# EASYEDA_Project_IOX_77_devboard_CG.net
KiCad netlist of a schematic drawn in EasyEDA Pro
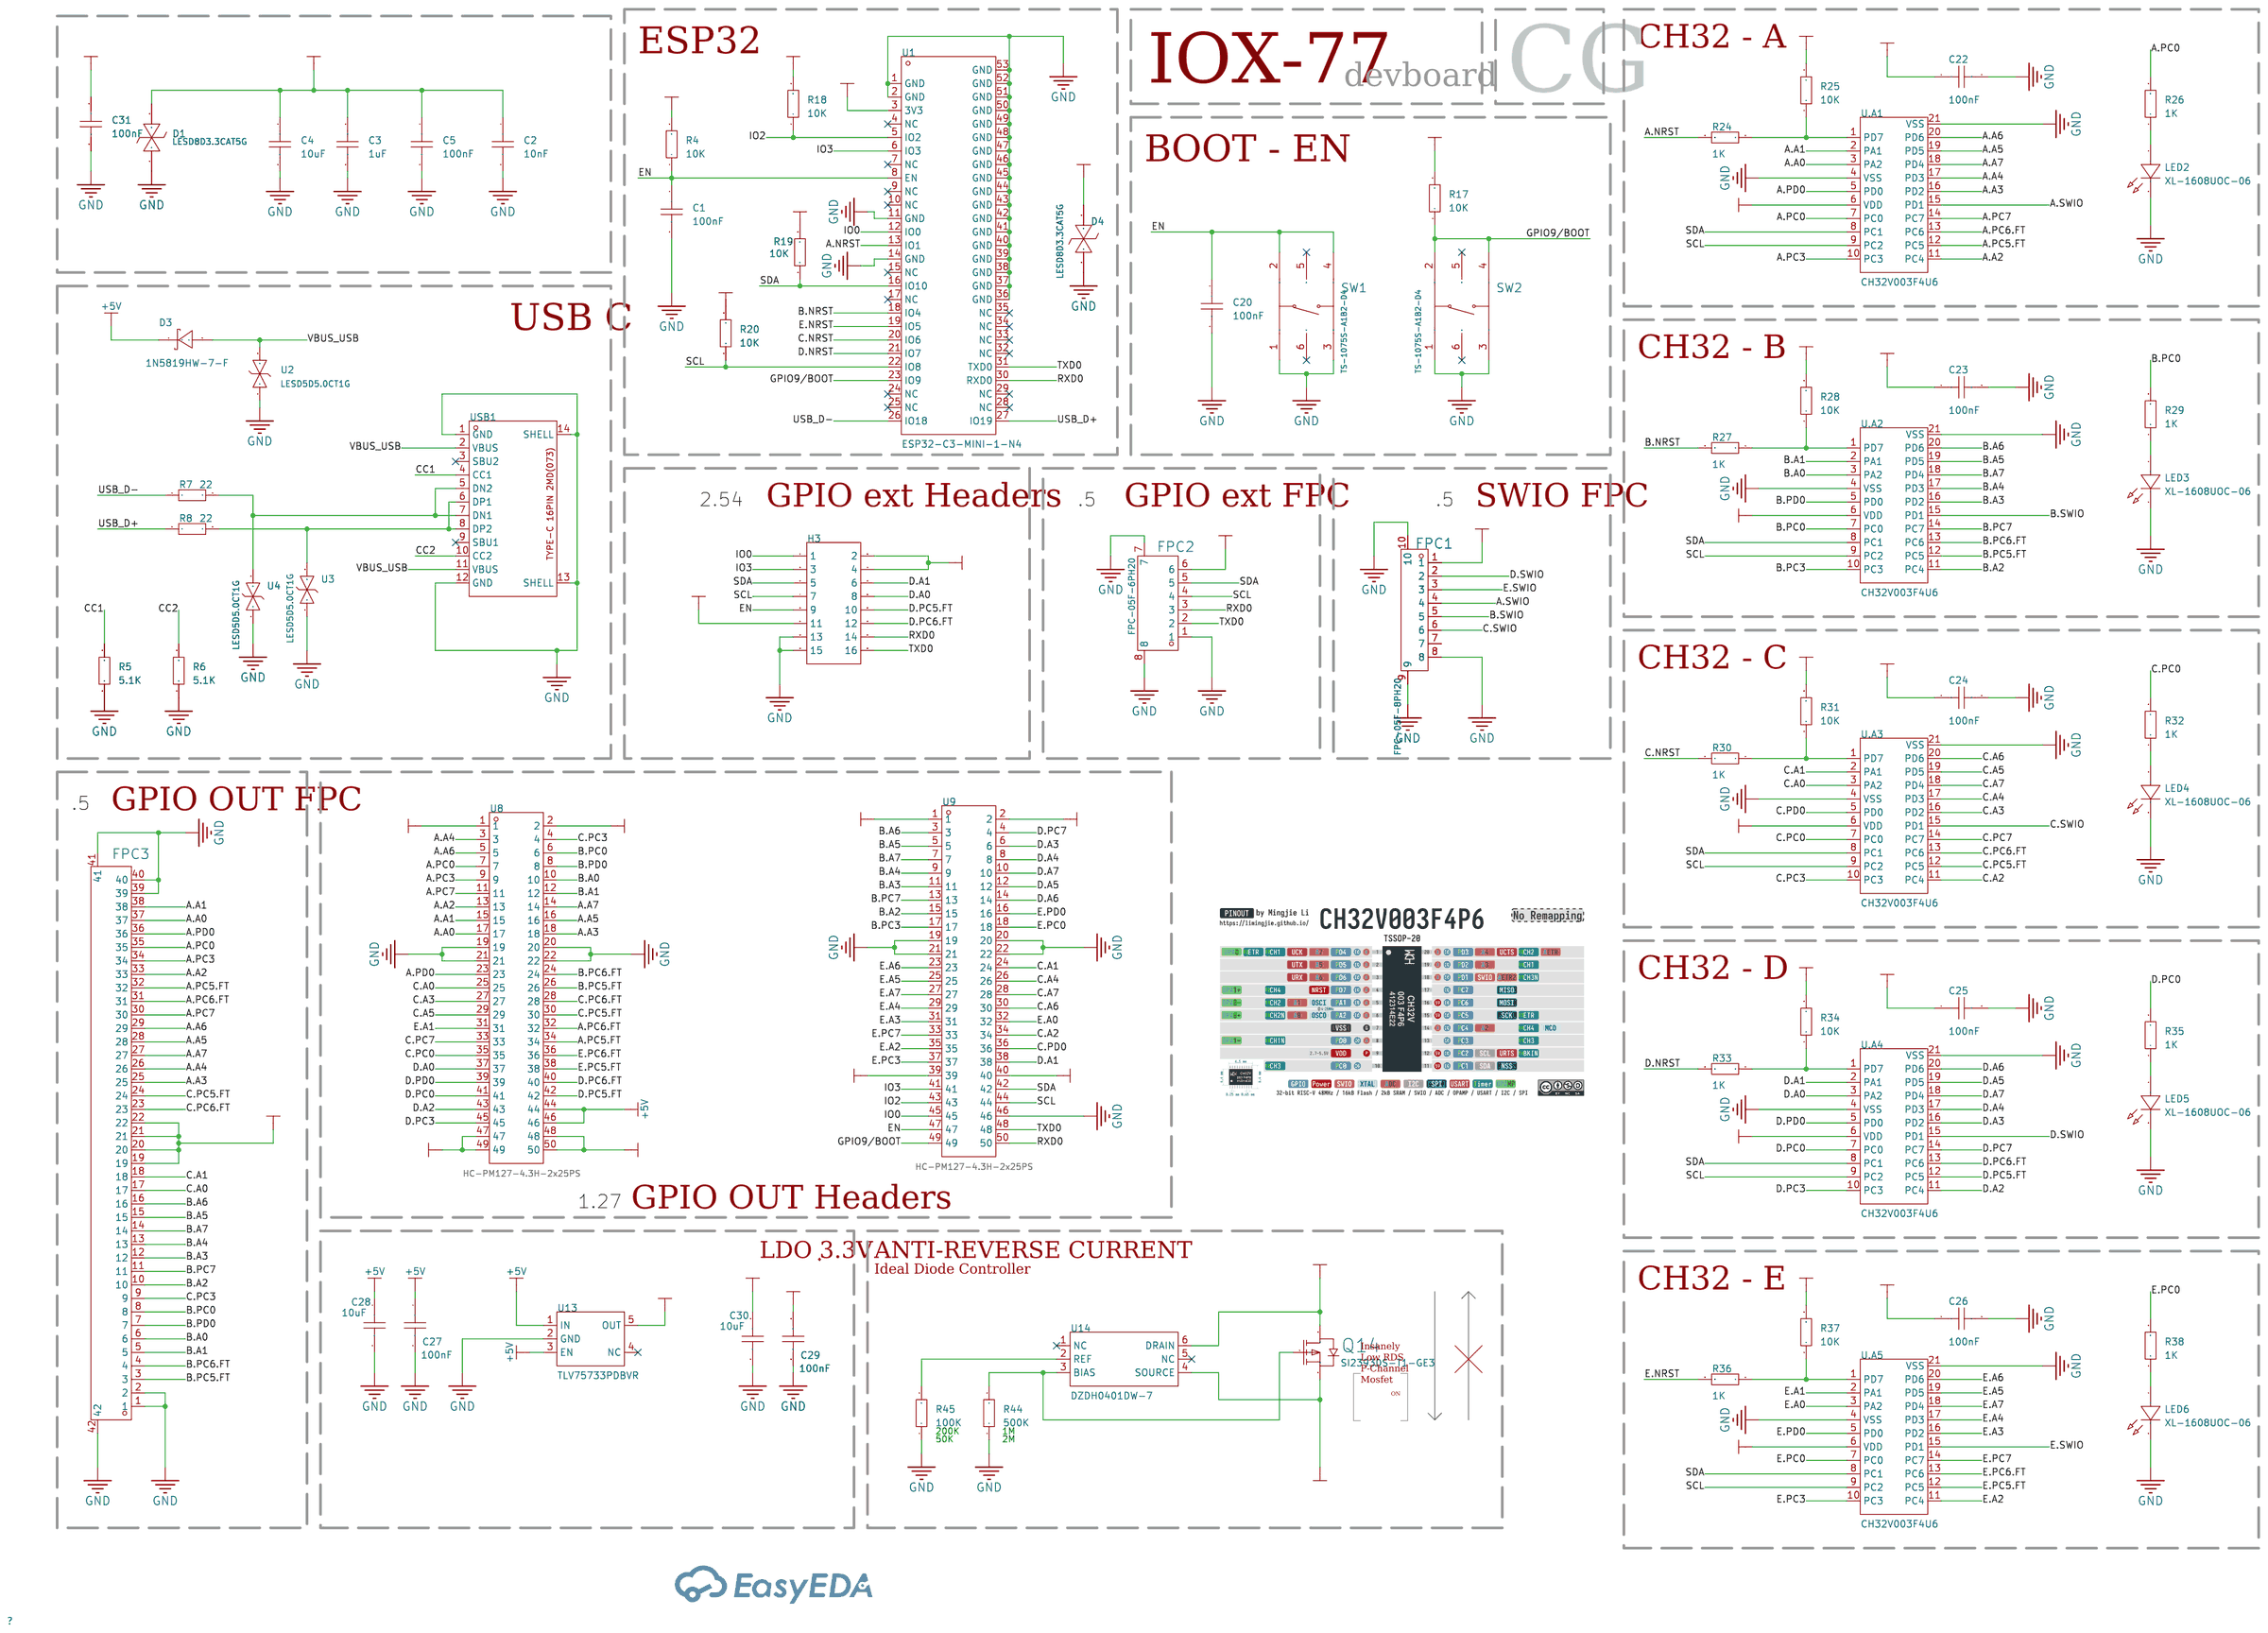
[diagram p0: schematic sheet]

(export (version "E")
  (design (tool "Eeschema 10.0.6"))
  (components
    (comp (ref "C1")
      (value "100nF")
      (footprint "easyedapro:C0603")
      (libsource (lib "easyedapro") (part "CAP"))
    )
    (comp (ref "C2")
      (value "10nF")
      (footprint "easyedapro:C0603")
      (description "Capacitance:10nF Tolerance:±10% Tolerance:±10% Voltage Rating:16V Temperature Coefficient:X7R")
      (fields
        (field (name "Manufacturer Part") "CC0603KRX7R7BB103")
        (field (name "Manufacturer") "YAGEO(国巨)")
      )
      (libsource (lib "easyedapro") (part "CAP"))
    )
    (comp (ref "C3")
      (value "1uF")
      (footprint "easyedapro:C0603")
      (description "Capacitance:1uF Tolerance:±10% Tolerance:±10% Voltage Rating:16V Temperature Coefficient:X5R")
      (fields
        (field (name "Manufacturer Part") "CL10A105KO8NNNC")
        (field (name "Manufacturer") "SAMSUNG(三星)")
      )
      (libsource (lib "easyedapro") (part "CAP"))
    )
    (comp (ref "C4")
      (value "10uF")
      (footprint "easyedapro:C0603")
      (description "Capacitance:10uF Tolerance:±10% Tolerance:±10% Voltage Rating:16V Temperature Coefficient:X5R")
      (fields
        (field (name "Manufacturer Part") "CL21A106KOQNNNE")
        (field (name "Manufacturer") "SAMSUNG(三星)")
      )
      (libsource (lib "easyedapro") (part "CAP"))
    )
    (comp (ref "C5")
      (value "100nF")
      (footprint "easyedapro:C0603")
      (description "Capacitance:100nF Tolerance:±10% Tolerance:±10% Voltage Rating:16V Temperature Coefficient:X7R")
      (fields
        (field (name "Manufacturer Part") "CL10B104KO8NNNC")
        (field (name "Manufacturer") "SAMSUNG(三星)")
      )
      (libsource (lib "easyedapro") (part "CAP"))
    )
    (comp (ref "C20")
      (value "100nF")
      (footprint "easyedapro:C0603")
      (description "Capacitance:100nF Tolerance:±10% Tolerance:±10% Voltage Rating:16V Temperature Coefficient:X7R")
      (fields
        (field (name "Manufacturer Part") "CL10B104KO8NNNC")
        (field (name "Manufacturer") "SAMSUNG(三星)")
      )
      (libsource (lib "easyedapro") (part "CAP"))
    )
    (comp (ref "C22")
      (value "100nF")
      (footprint "easyedapro:C0603")
      (description "Capacitance:100nF Tolerance:±10% Tolerance:±10% Voltage Rating:16V Temperature Coefficient:X7R")
      (fields
        (field (name "Manufacturer Part") "CL10B104KO8NNNC")
        (field (name "Manufacturer") "SAMSUNG(三星)")
      )
      (libsource (lib "easyedapro") (part "CAP"))
    )
    (comp (ref "C23")
      (value "100nF")
      (footprint "easyedapro:C0603")
      (description "Capacitance:100nF Tolerance:±10% Tolerance:±10% Voltage Rating:16V Temperature Coefficient:X7R")
      (fields
        (field (name "Manufacturer Part") "CL10B104KO8NNNC")
        (field (name "Manufacturer") "SAMSUNG(三星)")
      )
      (libsource (lib "easyedapro") (part "CAP"))
    )
    (comp (ref "C24")
      (value "100nF")
      (footprint "easyedapro:C0603")
      (description "Capacitance:100nF Tolerance:±10% Tolerance:±10% Voltage Rating:16V Temperature Coefficient:X7R")
      (fields
        (field (name "Manufacturer Part") "CL10B104KO8NNNC")
        (field (name "Manufacturer") "SAMSUNG(三星)")
      )
      (libsource (lib "easyedapro") (part "CAP"))
    )
    (comp (ref "C25")
      (value "100nF")
      (footprint "easyedapro:C0603")
      (description "Capacitance:100nF Tolerance:±10% Tolerance:±10% Voltage Rating:16V Temperature Coefficient:X7R")
      (fields
        (field (name "Manufacturer Part") "CL10B104KO8NNNC")
        (field (name "Manufacturer") "SAMSUNG(三星)")
      )
      (libsource (lib "easyedapro") (part "CAP"))
    )
    (comp (ref "C26")
      (value "100nF")
      (footprint "easyedapro:C0603")
      (description "Capacitance:100nF Tolerance:±10% Tolerance:±10% Voltage Rating:16V Temperature Coefficient:X7R")
      (fields
        (field (name "Manufacturer Part") "CL10B104KO8NNNC")
        (field (name "Manufacturer") "SAMSUNG(三星)")
      )
      (libsource (lib "easyedapro") (part "CAP"))
    )
    (comp (ref "C27")
      (value "100nF")
      (footprint "easyedapro:C0603")
      (description "Capacitance:100nF Tolerance:±10% Tolerance:±10% Voltage Rating:16V Temperature Coefficient:X7R")
      (fields
        (field (name "Manufacturer Part") "CL10B104KO8NNNC")
        (field (name "Manufacturer") "SAMSUNG(三星)")
      )
      (libsource (lib "easyedapro") (part "CAP"))
    )
    (comp (ref "C28")
      (value "10uF")
      (footprint "easyedapro:C0603")
      (description "Capacitance:10uF Tolerance:±10% Tolerance:±10% Voltage Rating:16V Temperature Coefficient:X5R")
      (fields
        (field (name "Manufacturer Part") "CL21A106KOQNNNE")
        (field (name "Manufacturer") "SAMSUNG(三星)")
      )
      (libsource (lib "easyedapro") (part "CAP"))
    )
    (comp (ref "C29")
      (value "100nF")
      (footprint "easyedapro:C0603")
      (description "Capacitance:100nF Tolerance:±10% Tolerance:±10% Voltage Rating:16V Temperature Coefficient:X7R")
      (fields
        (field (name "Manufacturer Part") "CL10B104KO8NNNC")
        (field (name "Manufacturer") "SAMSUNG(三星)")
      )
      (libsource (lib "easyedapro") (part "CAP"))
    )
    (comp (ref "C30")
      (value "10uF")
      (footprint "easyedapro:C0603")
      (description "Capacitance:10uF Tolerance:±10% Tolerance:±10% Voltage Rating:16V Temperature Coefficient:X5R")
      (fields
        (field (name "Manufacturer Part") "CL21A106KOQNNNE")
        (field (name "Manufacturer") "SAMSUNG(三星)")
      )
      (libsource (lib "easyedapro") (part "CAP"))
    )
    (comp (ref "C31")
      (value "100nF")
      (footprint "easyedapro:C0603")
      (description "Capacitance:10nF Tolerance:±10% Tolerance:±10% Voltage Rating:16V Temperature Coefficient:X7R")
      (fields
        (field (name "Manufacturer Part") "CC0603KRX7R7BB103")
        (field (name "Manufacturer") "YAGEO(国巨)")
      )
      (libsource (lib "easyedapro") (part "CAP"))
    )
    (comp (ref "D1")
      (value "LESD8D3.3CAT5G")
      (footprint "easyedapro:SOD-882_L1.0-W0.6-BI")
      (fields (field (name "Manufacturer") "FUXINSEMI(富芯森美)"))
      (libsource (lib "easyedapro") (part "LESD8D3.3CAT5G_C5563754"))
    )
    (comp (ref "D3")
      (value "1N5819HW-7-F")
      (footprint "easyedapro:SOD-123_L2.7-W1.6-LS3.7-RD")
      (fields (field (name "Manufacturer") "DIODES(美台)"))
      (libsource (lib "easyedapro") (part "1N5819HW-7-F"))
    )
    (comp (ref "D4")
      (value "LESD8D3.3CAT5G")
      (footprint "easyedapro:SOD-882_L1.0-W0.6-BI")
      (fields (field (name "Manufacturer") "FUXINSEMI(富芯森美)"))
      (libsource (lib "easyedapro") (part "LESD8D3.3CAT5G_C5563754"))
    )
    (comp (ref "FPC1")
      (value "FPC-05F-8PH20")
      (footprint "easyedapro:FPC-SMD_8P-P0.50_FPC-05F-8PH20")
      (fields (field (name "Manufacturer") "XUNPU(讯普)"))
      (libsource (lib "easyedapro") (part "FPC-05F-8PH20"))
    )
    (comp (ref "FPC2")
      (value "FPC-05F-6PH20")
      (footprint "easyedapro:FPC-SMD_6P-P0.50_XUNPU_FPC-05F-6PH20")
      (fields (field (name "Manufacturer") "XUNPU(讯普)"))
      (libsource (lib "easyedapro") (part "FPC-05F-6PH20"))
    )
    (comp (ref "FPC3")
      (value "FPC-05F-40PH20")
      (footprint "easyedapro:FPC-SMD_40P-P0.50_FPC-05F-40PH20")
      (fields (field (name "Manufacturer") "XUNPU(讯普)"))
      (libsource (lib "easyedapro") (part "FPC-05F-40PH20"))
    )
    (comp (ref "H3")
      (value "~")
      (footprint "easyedapro:HDR-TH_16P-P2.54-V-M-R2-C8-S2.54")
      (libsource (lib "easyedapro") (part "HDR-M-2.54_2x8"))
    )
    (comp (ref "LED2")
      (value "XL-1608UOC-06")
      (footprint "easyedapro:LED0603-R-RD_ORANGE")
      (fields (field (name "Manufacturer") "XINGLIGHT(成兴光)"))
      (libsource (lib "easyedapro") (part "XL-1608UOC-06"))
    )
    (comp (ref "LED3")
      (value "XL-1608UOC-06")
      (footprint "easyedapro:LED0603-R-RD_ORANGE")
      (fields (field (name "Manufacturer") "XINGLIGHT(成兴光)"))
      (libsource (lib "easyedapro") (part "XL-1608UOC-06"))
    )
    (comp (ref "LED4")
      (value "XL-1608UOC-06")
      (footprint "easyedapro:LED0603-R-RD_ORANGE")
      (fields (field (name "Manufacturer") "XINGLIGHT(成兴光)"))
      (libsource (lib "easyedapro") (part "XL-1608UOC-06"))
    )
    (comp (ref "LED5")
      (value "XL-1608UOC-06")
      (footprint "easyedapro:LED0603-R-RD_ORANGE")
      (fields (field (name "Manufacturer") "XINGLIGHT(成兴光)"))
      (libsource (lib "easyedapro") (part "XL-1608UOC-06"))
    )
    (comp (ref "LED6")
      (value "XL-1608UOC-06")
      (footprint "easyedapro:LED0603-R-RD_ORANGE")
      (fields (field (name "Manufacturer") "XINGLIGHT(成兴光)"))
      (libsource (lib "easyedapro") (part "XL-1608UOC-06"))
    )
    (comp (ref "Q14")
      (value "SI2393DS-T1-GE3")
      (footprint "easyedapro:SOT-23-3_L2.9-W1.3-P1.90-LS2.4-BR")
      (fields (field (name "Manufacturer") "VISHAY(威世)"))
      (libsource (lib "easyedapro") (part "SI2393DS-T1-GE3"))
    )
    (comp (ref "R4") (value "10K") (footprint "easyedapro:R0603") (libsource (lib "easyedapro") (part "Res")))
    (comp (ref "R5")
      (value "5.1K")
      (footprint "easyedapro:R0603")
      (libsource (lib "easyedapro") (part "Res"))
    )
    (comp (ref "R6")
      (value "5.1K")
      (footprint "easyedapro:R0603")
      (libsource (lib "easyedapro") (part "Res"))
    )
    (comp (ref "R7") (value "22") (footprint "easyedapro:R0603") (libsource (lib "easyedapro") (part "Res")))
    (comp (ref "R8") (value "22") (footprint "easyedapro:R0603") (libsource (lib "easyedapro") (part "Res")))
    (comp (ref "R17")
      (value "10K")
      (footprint "easyedapro:R0603")
      (libsource (lib "easyedapro") (part "Res"))
    )
    (comp (ref "R18")
      (value "10K")
      (footprint "easyedapro:R0603")
      (libsource (lib "easyedapro") (part "Res"))
    )
    (comp (ref "R19")
      (value "10K")
      (footprint "easyedapro:R0603")
      (libsource (lib "easyedapro") (part "Res"))
    )
    (comp (ref "R20")
      (value "10K")
      (footprint "easyedapro:R0603")
      (libsource (lib "easyedapro") (part "Res"))
    )
    (comp (ref "R24") (value "1K") (footprint "easyedapro:R0603") (libsource (lib "easyedapro") (part "Res")))
    (comp (ref "R25")
      (value "10K")
      (footprint "easyedapro:R0603")
      (libsource (lib "easyedapro") (part "Res"))
    )
    (comp (ref "R26") (value "1K") (footprint "easyedapro:R0603") (libsource (lib "easyedapro") (part "Res")))
    (comp (ref "R27") (value "1K") (footprint "easyedapro:R0603") (libsource (lib "easyedapro") (part "Res")))
    (comp (ref "R28")
      (value "10K")
      (footprint "easyedapro:R0603")
      (libsource (lib "easyedapro") (part "Res"))
    )
    (comp (ref "R29") (value "1K") (footprint "easyedapro:R0603") (libsource (lib "easyedapro") (part "Res")))
    (comp (ref "R30") (value "1K") (footprint "easyedapro:R0603") (libsource (lib "easyedapro") (part "Res")))
    (comp (ref "R31")
      (value "10K")
      (footprint "easyedapro:R0603")
      (libsource (lib "easyedapro") (part "Res"))
    )
    (comp (ref "R32") (value "1K") (footprint "easyedapro:R0603") (libsource (lib "easyedapro") (part "Res")))
    (comp (ref "R33") (value "1K") (footprint "easyedapro:R0603") (libsource (lib "easyedapro") (part "Res")))
    (comp (ref "R34")
      (value "10K")
      (footprint "easyedapro:R0603")
      (libsource (lib "easyedapro") (part "Res"))
    )
    (comp (ref "R35") (value "1K") (footprint "easyedapro:R0603") (libsource (lib "easyedapro") (part "Res")))
    (comp (ref "R36") (value "1K") (footprint "easyedapro:R0603") (libsource (lib "easyedapro") (part "Res")))
    (comp (ref "R37")
      (value "10K")
      (footprint "easyedapro:R0603")
      (libsource (lib "easyedapro") (part "Res"))
    )
    (comp (ref "R38") (value "1K") (footprint "easyedapro:R0603") (libsource (lib "easyedapro") (part "Res")))
    (comp (ref "R44")
      (value "500K")
      (footprint "easyedapro:R0603")
      (libsource (lib "easyedapro") (part "Res"))
    )
    (comp (ref "R45")
      (value "100K")
      (footprint "easyedapro:R0603")
      (libsource (lib "easyedapro") (part "Res"))
    )
    (comp (ref "SW1")
      (value "TS-1075S-A1B2-D4")
      (footprint "easyedapro:SW-SMD_4P-L3.1-W3.1-P2.20-LS4.0")
      (fields (field (name "Manufacturer") "Yuandi(元迪)"))
      (libsource (lib "easyedapro") (part "TS-1075S-A1B2-D4"))
    )
    (comp (ref "SW2")
      (value "TS-1075S-A1B2-D4")
      (footprint "easyedapro:SW-SMD_4P-L3.1-W3.1-P2.20-LS4.0")
      (fields (field (name "Manufacturer") "Yuandi(元迪)"))
      (libsource (lib "easyedapro") (part "TS-1075S-A1B2-D4"))
    )
    (comp (ref "U.A1")
      (value "CH32V003F4U6")
      (footprint "easyedapro:QFN-20_L3.0-W3.0-P0.40-TL-EP1.7")
      (description "CPU Core:RISC-V CPU Maximum Speed:48MHz Program Storage Size:16KB Number of I/O:18 Applications:-")
      (fields (field (name "Manufacturer") "WCH(南京沁恒)"))
      (libsource (lib "easyedapro") (part "CH32V003F4U6"))
    )
    (comp (ref "U.A2")
      (value "CH32V003F4U6")
      (footprint "easyedapro:QFN-20_L3.0-W3.0-P0.40-TL-EP1.7")
      (description "CPU Core:RISC-V CPU Maximum Speed:48MHz Program Storage Size:16KB Number of I/O:18 Applications:-")
      (fields (field (name "Manufacturer") "WCH(南京沁恒)"))
      (libsource (lib "easyedapro") (part "CH32V003F4U6"))
    )
    (comp (ref "U.A3")
      (value "CH32V003F4U6")
      (footprint "easyedapro:QFN-20_L3.0-W3.0-P0.40-TL-EP1.7")
      (description "CPU Core:RISC-V CPU Maximum Speed:48MHz Program Storage Size:16KB Number of I/O:18 Applications:-")
      (fields (field (name "Manufacturer") "WCH(南京沁恒)"))
      (libsource (lib "easyedapro") (part "CH32V003F4U6"))
    )
    (comp (ref "U.A4")
      (value "CH32V003F4U6")
      (footprint "easyedapro:QFN-20_L3.0-W3.0-P0.40-TL-EP1.7")
      (description "CPU Core:RISC-V CPU Maximum Speed:48MHz Program Storage Size:16KB Number of I/O:18 Applications:-")
      (fields (field (name "Manufacturer") "WCH(南京沁恒)"))
      (libsource (lib "easyedapro") (part "CH32V003F4U6"))
    )
    (comp (ref "U.A5")
      (value "CH32V003F4U6")
      (footprint "easyedapro:QFN-20_L3.0-W3.0-P0.40-TL-EP1.7")
      (description "CPU Core:RISC-V CPU Maximum Speed:48MHz Program Storage Size:16KB Number of I/O:18 Applications:-")
      (fields (field (name "Manufacturer") "WCH(南京沁恒)"))
      (libsource (lib "easyedapro") (part "CH32V003F4U6"))
    )
    (comp (ref "U1")
      (value "ESP32-C3-MINI-1-N4")
      (footprint "easyedapro:WIFIM-SMD_ESP32-C3-MINI-1")
      (fields (field (name "Manufacturer") "ESPRESSIF(乐鑫)"))
      (libsource (lib "easyedapro") (part "ESP32-C3-MINI-1-N4"))
    )
    (comp (ref "U2")
      (value "LESD5D5.0CT1G")
      (footprint "easyedapro:SOD-523_L1.2-W0.8-LS1.6-BI")
      (fields (field (name "Manufacturer") "KUU"))
      (libsource (lib "easyedapro") (part "LESD5D5.0CT1G_C7433850"))
    )
    (comp (ref "U3")
      (value "LESD5D5.0CT1G")
      (footprint "easyedapro:SOD-523_L1.2-W0.8-LS1.6-BI")
      (fields (field (name "Manufacturer") "KUU"))
      (libsource (lib "easyedapro") (part "LESD5D5.0CT1G_C7433850"))
    )
    (comp (ref "U4")
      (value "LESD5D5.0CT1G")
      (footprint "easyedapro:SOD-523_L1.2-W0.8-LS1.6-BI")
      (fields (field (name "Manufacturer") "KUU"))
      (libsource (lib "easyedapro") (part "LESD5D5.0CT1G_C7433850"))
    )
    (comp (ref "U8")
      (value "HC-PM127-4.3H-2x25PS")
      (footprint "easyedapro:HDR-SMD_50P-P1.27-V-F-R2-C25-LS4.8")
      (fields (field (name "Manufacturer") "HC(虹成电子)"))
      (libsource (lib "easyedapro") (part "HC-PM127-4.3H-2X25PS"))
    )
    (comp (ref "U9")
      (value "HC-PM127-4.3H-2x25PS")
      (footprint "easyedapro:HDR-SMD_50P-P1.27-V-F-R2-C25-LS4.8")
      (fields (field (name "Manufacturer") "HC(虹成电子)"))
      (libsource (lib "easyedapro") (part "HC-PM127-4.3H-2X25PS"))
    )
    (comp (ref "U13")
      (value "TLV75733PDBVR")
      (footprint "easyedapro:SOT-23-5_L2.9-W1.6-P0.95-LS2.8-BL")
      (fields (field (name "Manufacturer") "TI(德州仪器)"))
      (libsource (lib "easyedapro") (part "TLV75733PDBVR"))
    )
    (comp (ref "U14")
      (value "DZDH0401DW-7")
      (footprint "easyedapro:SOT-363_L2.0-W1.3-P0.65-LS2.1-BR")
      (fields (field (name "Manufacturer") "DIODES(美台)"))
      (libsource (lib "easyedapro") (part "DZDH0401DW-7"))
    )
    (comp (ref "USB1")
      (value "TYPE-C 16PIN 2MD(073)")
      (footprint "easyedapro:USB-C-SMD_TYPE-C-6PIN-2MD-073")
      (fields (field (name "Manufacturer") "SHOU HAN(首韩)"))
      (libsource (lib "easyedapro") (part "TYPE-C 16PIN 2MD(073)"))
    )
  )
  (nets
    (net (code "1") (name "+3.3V") (class "Default")
      (node (ref "C2") (pin "1") (pinfunction "1_1") (pintype "input"))
      (node (ref "C22") (pin "1") (pinfunction "1_1") (pintype "input"))
      (node (ref "C23") (pin "1") (pinfunction "1_1") (pintype "input"))
      (node (ref "C24") (pin "1") (pinfunction "1_1") (pintype "input"))
      (node (ref "C25") (pin "1") (pinfunction "1_1") (pintype "input"))
      (node (ref "C26") (pin "1") (pinfunction "1_1") (pintype "input"))
      (node (ref "C3") (pin "1") (pinfunction "1_1") (pintype "input"))
      (node (ref "C31") (pin "1") (pinfunction "1_1") (pintype "input"))
      (node (ref "C4") (pin "1") (pinfunction "1_1") (pintype "input"))
      (node (ref "C5") (pin "1") (pinfunction "1_1") (pintype "input"))
      (node (ref "D1") (pin "2") (pinfunction "2_2") (pintype "unspecified"))
      (node (ref "D4") (pin "2") (pinfunction "2_2") (pintype "unspecified"))
      (node (ref "FPC1") (pin "1") (pinfunction "1_1") (pintype "unspecified"))
      (node (ref "FPC2") (pin "6") (pinfunction "6_6") (pintype "input"))
      (node (ref "FPC3") (pin "19") (pinfunction "19_19") (pintype "input"))
      (node (ref "FPC3") (pin "20") (pinfunction "20_20") (pintype "input"))
      (node (ref "FPC3") (pin "21") (pinfunction "21_21") (pintype "input"))
      (node (ref "FPC3") (pin "22") (pinfunction "22_22") (pintype "input"))
      (node (ref "H3") (pin "2") (pinfunction "2_2") (pintype "input"))
      (node (ref "H3") (pin "4") (pinfunction "4_4") (pintype "input"))
      (node (ref "Q14") (pin "2") (pinfunction "S_2") (pintype "unspecified"))
      (node (ref "R17") (pin "2") (pinfunction "2_2") (pintype "input"))
      (node (ref "R18") (pin "2") (pinfunction "2_2") (pintype "input"))
      (node (ref "R19") (pin "2") (pinfunction "2_2") (pintype "input"))
      (node (ref "R20") (pin "2") (pinfunction "2_2") (pintype "input"))
      (node (ref "R25") (pin "2") (pinfunction "2_2") (pintype "input"))
      (node (ref "R28") (pin "2") (pinfunction "2_2") (pintype "input"))
      (node (ref "R31") (pin "2") (pinfunction "2_2") (pintype "input"))
      (node (ref "R34") (pin "2") (pinfunction "2_2") (pintype "input"))
      (node (ref "R37") (pin "2") (pinfunction "2_2") (pintype "input"))
      (node (ref "R4") (pin "2") (pinfunction "2_2") (pintype "input"))
      (node (ref "U.A1") (pin "6") (pinfunction "VDD_6") (pintype "unspecified"))
      (node (ref "U.A2") (pin "6") (pinfunction "VDD_6") (pintype "unspecified"))
      (node (ref "U.A3") (pin "6") (pinfunction "VDD_6") (pintype "unspecified"))
      (node (ref "U.A4") (pin "6") (pinfunction "VDD_6") (pintype "unspecified"))
      (node (ref "U.A5") (pin "6") (pinfunction "VDD_6") (pintype "unspecified"))
      (node (ref "U1") (pin "3") (pinfunction "3V3_3") (pintype "unspecified"))
      (node (ref "U14") (pin "4") (pinfunction "SOURCE_4") (pintype "unspecified"))
      (node (ref "U8") (pin "1") (pinfunction "1_1") (pintype "unspecified"))
      (node (ref "U8") (pin "2") (pinfunction "2_2") (pintype "unspecified"))
      (node (ref "U8") (pin "47") (pinfunction "47_47") (pintype "unspecified"))
      (node (ref "U8") (pin "48") (pinfunction "48_48") (pintype "unspecified"))
      (node (ref "U8") (pin "49") (pinfunction "49_49") (pintype "unspecified"))
      (node (ref "U8") (pin "50") (pinfunction "50_50") (pintype "unspecified"))
      (node (ref "U9") (pin "1") (pinfunction "1_1") (pintype "unspecified"))
      (node (ref "U9") (pin "2") (pinfunction "2_2") (pintype "unspecified"))
      (node (ref "U9") (pin "39") (pinfunction "39_39") (pintype "unspecified"))
      (node (ref "U9") (pin "40") (pinfunction "40_40") (pintype "unspecified"))
    )
    (net (code "2") (name "+3.3V.LDO") (class "Default")
      (node (ref "C29") (pin "1") (pinfunction "1_1") (pintype "input"))
      (node (ref "C30") (pin "1") (pinfunction "1_1") (pintype "input"))
      (node (ref "Q14") (pin "3") (pinfunction "D_3") (pintype "unspecified"))
      (node (ref "U13") (pin "5") (pinfunction "OUT_5") (pintype "unspecified"))
      (node (ref "U14") (pin "6") (pinfunction "DRAIN_6") (pintype "unspecified"))
    )
    (net (code "3") (name "+5V") (class "Default")
      (node (ref "C27") (pin "1") (pinfunction "1_1") (pintype "input"))
      (node (ref "C28") (pin "1") (pinfunction "1_1") (pintype "input"))
      (node (ref "D3") (pin "1") (pinfunction "K_1") (pintype "unspecified"))
      (node (ref "H3") (pin "11") (pinfunction "11_11") (pintype "input"))
      (node (ref "U13") (pin "1") (pinfunction "IN_1") (pintype "unspecified"))
      (node (ref "U13") (pin "3") (pinfunction "EN_3") (pintype "unspecified"))
      (node (ref "U8") (pin "44") (pinfunction "44_44") (pintype "unspecified"))
      (node (ref "U8") (pin "46") (pinfunction "46_46") (pintype "unspecified"))
    )
    (net (code "4") (name "/A.A0") (class "Default")
      (node (ref "FPC3") (pin "37") (pinfunction "37_37") (pintype "input"))
      (node (ref "U.A1") (pin "3") (pinfunction "PA2_3") (pintype "unspecified"))
      (node (ref "U8") (pin "17") (pinfunction "17_17") (pintype "unspecified"))
    )
    (net (code "5") (name "/A.A1") (class "Default")
      (node (ref "FPC3") (pin "38") (pinfunction "38_38") (pintype "input"))
      (node (ref "U.A1") (pin "2") (pinfunction "PA1_2") (pintype "unspecified"))
      (node (ref "U8") (pin "15") (pinfunction "15_15") (pintype "unspecified"))
    )
    (net (code "6") (name "/A.A2") (class "Default")
      (node (ref "FPC3") (pin "33") (pinfunction "33_33") (pintype "input"))
      (node (ref "U.A1") (pin "11") (pinfunction "PC4_11") (pintype "unspecified"))
      (node (ref "U8") (pin "13") (pinfunction "13_13") (pintype "unspecified"))
    )
    (net (code "7") (name "/A.A3") (class "Default")
      (node (ref "FPC3") (pin "25") (pinfunction "25_25") (pintype "input"))
      (node (ref "U.A1") (pin "16") (pinfunction "PD2_16") (pintype "unspecified"))
      (node (ref "U8") (pin "18") (pinfunction "18_18") (pintype "unspecified"))
    )
    (net (code "8") (name "/A.A4") (class "Default")
      (node (ref "FPC3") (pin "26") (pinfunction "26_26") (pintype "input"))
      (node (ref "U.A1") (pin "17") (pinfunction "PD3_17") (pintype "unspecified"))
      (node (ref "U8") (pin "3") (pinfunction "3_3") (pintype "unspecified"))
    )
    (net (code "9") (name "/A.A5") (class "Default")
      (node (ref "FPC3") (pin "28") (pinfunction "28_28") (pintype "input"))
      (node (ref "U.A1") (pin "19") (pinfunction "PD5_19") (pintype "unspecified"))
      (node (ref "U8") (pin "16") (pinfunction "16_16") (pintype "unspecified"))
    )
    (net (code "10") (name "/A.A6") (class "Default")
      (node (ref "FPC3") (pin "29") (pinfunction "29_29") (pintype "input"))
      (node (ref "U.A1") (pin "20") (pinfunction "PD6_20") (pintype "unspecified"))
      (node (ref "U8") (pin "5") (pinfunction "5_5") (pintype "unspecified"))
    )
    (net (code "11") (name "/A.A7") (class "Default")
      (node (ref "FPC3") (pin "27") (pinfunction "27_27") (pintype "input"))
      (node (ref "U.A1") (pin "18") (pinfunction "PD4_18") (pintype "unspecified"))
      (node (ref "U8") (pin "14") (pinfunction "14_14") (pintype "unspecified"))
    )
    (net (code "12") (name "/A.NRST") (class "Default")
      (node (ref "R24") (pin "2") (pinfunction "2_2") (pintype "input"))
      (node (ref "U1") (pin "13") (pinfunction "IO1_13") (pintype "unspecified"))
    )
    (net (code "13") (name "/A.PC0") (class "Default")
      (node (ref "FPC3") (pin "35") (pinfunction "35_35") (pintype "input"))
      (node (ref "R26") (pin "2") (pinfunction "2_2") (pintype "input"))
      (node (ref "U.A1") (pin "7") (pinfunction "PC0_7") (pintype "unspecified"))
      (node (ref "U8") (pin "7") (pinfunction "7_7") (pintype "unspecified"))
    )
    (net (code "14") (name "/A.PC3") (class "Default")
      (node (ref "FPC3") (pin "34") (pinfunction "34_34") (pintype "input"))
      (node (ref "U.A1") (pin "10") (pinfunction "PC3_10") (pintype "unspecified"))
      (node (ref "U8") (pin "9") (pinfunction "9_9") (pintype "unspecified"))
    )
    (net (code "15") (name "/A.PC5.FT") (class "Default")
      (node (ref "FPC3") (pin "32") (pinfunction "32_32") (pintype "input"))
      (node (ref "U.A1") (pin "12") (pinfunction "PC5_12") (pintype "unspecified"))
      (node (ref "U8") (pin "34") (pinfunction "34_34") (pintype "unspecified"))
    )
    (net (code "16") (name "/A.PC6.FT") (class "Default")
      (node (ref "FPC3") (pin "31") (pinfunction "31_31") (pintype "input"))
      (node (ref "U.A1") (pin "13") (pinfunction "PC6_13") (pintype "unspecified"))
      (node (ref "U8") (pin "32") (pinfunction "32_32") (pintype "unspecified"))
    )
    (net (code "17") (name "/A.PC7") (class "Default")
      (node (ref "FPC3") (pin "30") (pinfunction "30_30") (pintype "input"))
      (node (ref "U.A1") (pin "14") (pinfunction "PC7_14") (pintype "unspecified"))
      (node (ref "U8") (pin "11") (pinfunction "11_11") (pintype "unspecified"))
    )
    (net (code "18") (name "/A.PD0") (class "Default")
      (node (ref "FPC3") (pin "36") (pinfunction "36_36") (pintype "input"))
      (node (ref "U.A1") (pin "5") (pinfunction "PD0_5") (pintype "unspecified"))
      (node (ref "U8") (pin "23") (pinfunction "23_23") (pintype "unspecified"))
    )
    (net (code "19") (name "/A.SWIO") (class "Default")
      (node (ref "FPC1") (pin "4") (pinfunction "4_4") (pintype "unspecified"))
      (node (ref "U.A1") (pin "15") (pinfunction "PD1_15") (pintype "unspecified"))
    )
    (net (code "20") (name "/B.A0") (class "Default")
      (node (ref "FPC3") (pin "6") (pinfunction "6_6") (pintype "input"))
      (node (ref "U.A2") (pin "3") (pinfunction "PA2_3") (pintype "unspecified"))
      (node (ref "U8") (pin "10") (pinfunction "10_10") (pintype "unspecified"))
    )
    (net (code "21") (name "/B.A1") (class "Default")
      (node (ref "FPC3") (pin "5") (pinfunction "5_5") (pintype "input"))
      (node (ref "U.A2") (pin "2") (pinfunction "PA1_2") (pintype "unspecified"))
      (node (ref "U8") (pin "12") (pinfunction "12_12") (pintype "unspecified"))
    )
    (net (code "22") (name "/B.A2") (class "Default")
      (node (ref "FPC3") (pin "10") (pinfunction "10_10") (pintype "input"))
      (node (ref "U.A2") (pin "11") (pinfunction "PC4_11") (pintype "unspecified"))
      (node (ref "U9") (pin "15") (pinfunction "15_15") (pintype "unspecified"))
    )
    (net (code "23") (name "/B.A3") (class "Default")
      (node (ref "FPC3") (pin "12") (pinfunction "12_12") (pintype "input"))
      (node (ref "U.A2") (pin "16") (pinfunction "PD2_16") (pintype "unspecified"))
      (node (ref "U9") (pin "11") (pinfunction "11_11") (pintype "unspecified"))
    )
    (net (code "24") (name "/B.A4") (class "Default")
      (node (ref "FPC3") (pin "13") (pinfunction "13_13") (pintype "input"))
      (node (ref "U.A2") (pin "17") (pinfunction "PD3_17") (pintype "unspecified"))
      (node (ref "U9") (pin "9") (pinfunction "9_9") (pintype "unspecified"))
    )
    (net (code "25") (name "/B.A5") (class "Default")
      (node (ref "FPC3") (pin "15") (pinfunction "15_15") (pintype "input"))
      (node (ref "U.A2") (pin "19") (pinfunction "PD5_19") (pintype "unspecified"))
      (node (ref "U9") (pin "5") (pinfunction "5_5") (pintype "unspecified"))
    )
    (net (code "26") (name "/B.A6") (class "Default")
      (node (ref "FPC3") (pin "16") (pinfunction "16_16") (pintype "input"))
      (node (ref "U.A2") (pin "20") (pinfunction "PD6_20") (pintype "unspecified"))
      (node (ref "U9") (pin "3") (pinfunction "3_3") (pintype "unspecified"))
    )
    (net (code "27") (name "/B.A7") (class "Default")
      (node (ref "FPC3") (pin "14") (pinfunction "14_14") (pintype "input"))
      (node (ref "U.A2") (pin "18") (pinfunction "PD4_18") (pintype "unspecified"))
      (node (ref "U9") (pin "7") (pinfunction "7_7") (pintype "unspecified"))
    )
    (net (code "28") (name "/B.NRST") (class "Default")
      (node (ref "R27") (pin "2") (pinfunction "2_2") (pintype "input"))
      (node (ref "U1") (pin "18") (pinfunction "IO4_18") (pintype "unspecified"))
    )
    (net (code "29") (name "/B.PC0") (class "Default")
      (node (ref "FPC3") (pin "8") (pinfunction "8_8") (pintype "input"))
      (node (ref "R29") (pin "2") (pinfunction "2_2") (pintype "input"))
      (node (ref "U.A2") (pin "7") (pinfunction "PC0_7") (pintype "unspecified"))
      (node (ref "U8") (pin "6") (pinfunction "6_6") (pintype "unspecified"))
    )
    (net (code "30") (name "/B.PC3") (class "Default")
      (node (ref "U.A2") (pin "10") (pinfunction "PC3_10") (pintype "unspecified"))
      (node (ref "U9") (pin "17") (pinfunction "17_17") (pintype "unspecified"))
    )
    (net (code "31") (name "/B.PC5.FT") (class "Default")
      (node (ref "FPC3") (pin "3") (pinfunction "3_3") (pintype "input"))
      (node (ref "U.A2") (pin "12") (pinfunction "PC5_12") (pintype "unspecified"))
      (node (ref "U8") (pin "26") (pinfunction "26_26") (pintype "unspecified"))
    )
    (net (code "32") (name "/B.PC6.FT") (class "Default")
      (node (ref "FPC3") (pin "4") (pinfunction "4_4") (pintype "input"))
      (node (ref "U.A2") (pin "13") (pinfunction "PC6_13") (pintype "unspecified"))
      (node (ref "U8") (pin "24") (pinfunction "24_24") (pintype "unspecified"))
    )
    (net (code "33") (name "/B.PC7") (class "Default")
      (node (ref "FPC3") (pin "11") (pinfunction "11_11") (pintype "input"))
      (node (ref "U.A2") (pin "14") (pinfunction "PC7_14") (pintype "unspecified"))
      (node (ref "U9") (pin "13") (pinfunction "13_13") (pintype "unspecified"))
    )
    (net (code "34") (name "/B.PD0") (class "Default")
      (node (ref "FPC3") (pin "7") (pinfunction "7_7") (pintype "input"))
      (node (ref "U.A2") (pin "5") (pinfunction "PD0_5") (pintype "unspecified"))
      (node (ref "U8") (pin "8") (pinfunction "8_8") (pintype "unspecified"))
    )
    (net (code "35") (name "/B.SWIO") (class "Default")
      (node (ref "FPC1") (pin "5") (pinfunction "5_5") (pintype "unspecified"))
      (node (ref "U.A2") (pin "15") (pinfunction "PD1_15") (pintype "unspecified"))
    )
    (net (code "36") (name "/C.A0") (class "Default")
      (node (ref "FPC3") (pin "17") (pinfunction "17_17") (pintype "input"))
      (node (ref "U.A3") (pin "3") (pinfunction "PA2_3") (pintype "unspecified"))
      (node (ref "U8") (pin "25") (pinfunction "25_25") (pintype "unspecified"))
    )
    (net (code "37") (name "/C.A1") (class "Default")
      (node (ref "FPC3") (pin "18") (pinfunction "18_18") (pintype "input"))
      (node (ref "U.A3") (pin "2") (pinfunction "PA1_2") (pintype "unspecified"))
      (node (ref "U9") (pin "24") (pinfunction "24_24") (pintype "unspecified"))
    )
    (net (code "38") (name "/C.A2") (class "Default")
      (node (ref "U.A3") (pin "11") (pinfunction "PC4_11") (pintype "unspecified"))
      (node (ref "U9") (pin "34") (pinfunction "34_34") (pintype "unspecified"))
    )
    (net (code "39") (name "/C.A3") (class "Default")
      (node (ref "U.A3") (pin "16") (pinfunction "PD2_16") (pintype "unspecified"))
      (node (ref "U8") (pin "27") (pinfunction "27_27") (pintype "unspecified"))
    )
    (net (code "40") (name "/C.A4") (class "Default")
      (node (ref "U.A3") (pin "17") (pinfunction "PD3_17") (pintype "unspecified"))
      (node (ref "U9") (pin "26") (pinfunction "26_26") (pintype "unspecified"))
    )
    (net (code "41") (name "/C.A5") (class "Default")
      (node (ref "U.A3") (pin "19") (pinfunction "PD5_19") (pintype "unspecified"))
      (node (ref "U8") (pin "29") (pinfunction "29_29") (pintype "unspecified"))
    )
    (net (code "42") (name "/C.A6") (class "Default")
      (node (ref "U.A3") (pin "20") (pinfunction "PD6_20") (pintype "unspecified"))
      (node (ref "U9") (pin "30") (pinfunction "30_30") (pintype "unspecified"))
    )
    (net (code "43") (name "/C.A7") (class "Default")
      (node (ref "U.A3") (pin "18") (pinfunction "PD4_18") (pintype "unspecified"))
      (node (ref "U9") (pin "28") (pinfunction "28_28") (pintype "unspecified"))
    )
    (net (code "44") (name "/C.NRST") (class "Default")
      (node (ref "R30") (pin "2") (pinfunction "2_2") (pintype "input"))
      (node (ref "U1") (pin "20") (pinfunction "IO6_20") (pintype "unspecified"))
    )
    (net (code "45") (name "/C.PC0") (class "Default")
      (node (ref "R32") (pin "2") (pinfunction "2_2") (pintype "input"))
      (node (ref "U.A3") (pin "7") (pinfunction "PC0_7") (pintype "unspecified"))
      (node (ref "U8") (pin "35") (pinfunction "35_35") (pintype "unspecified"))
    )
    (net (code "46") (name "/C.PC3") (class "Default")
      (node (ref "FPC3") (pin "9") (pinfunction "9_9") (pintype "input"))
      (node (ref "U.A3") (pin "10") (pinfunction "PC3_10") (pintype "unspecified"))
      (node (ref "U8") (pin "4") (pinfunction "4_4") (pintype "unspecified"))
    )
    (net (code "47") (name "/C.PC5.FT") (class "Default")
      (node (ref "FPC3") (pin "24") (pinfunction "24_24") (pintype "input"))
      (node (ref "U.A3") (pin "12") (pinfunction "PC5_12") (pintype "unspecified"))
      (node (ref "U8") (pin "30") (pinfunction "30_30") (pintype "unspecified"))
    )
    (net (code "48") (name "/C.PC6.FT") (class "Default")
      (node (ref "FPC3") (pin "23") (pinfunction "23_23") (pintype "input"))
      (node (ref "U.A3") (pin "13") (pinfunction "PC6_13") (pintype "unspecified"))
      (node (ref "U8") (pin "28") (pinfunction "28_28") (pintype "unspecified"))
    )
    (net (code "49") (name "/C.PC7") (class "Default")
      (node (ref "U.A3") (pin "14") (pinfunction "PC7_14") (pintype "unspecified"))
      (node (ref "U8") (pin "33") (pinfunction "33_33") (pintype "unspecified"))
    )
    (net (code "50") (name "/C.PD0") (class "Default")
      (node (ref "U.A3") (pin "5") (pinfunction "PD0_5") (pintype "unspecified"))
      (node (ref "U9") (pin "36") (pinfunction "36_36") (pintype "unspecified"))
    )
    (net (code "51") (name "/C.SWIO") (class "Default")
      (node (ref "FPC1") (pin "6") (pinfunction "6_6") (pintype "unspecified"))
      (node (ref "U.A3") (pin "15") (pinfunction "PD1_15") (pintype "unspecified"))
    )
    (net (code "52") (name "/CC1") (class "Default")
      (node (ref "R5") (pin "2") (pinfunction "2_2") (pintype "input"))
      (node (ref "USB1") (pin "4") (pinfunction "CC1_4") (pintype "unspecified"))
    )
    (net (code "53") (name "/CC2") (class "Default")
      (node (ref "R6") (pin "2") (pinfunction "2_2") (pintype "input"))
      (node (ref "USB1") (pin "10") (pinfunction "CC2_10") (pintype "unspecified"))
    )
    (net (code "54") (name "/D.A0") (class "Default")
      (node (ref "H3") (pin "8") (pinfunction "8_8") (pintype "input"))
      (node (ref "U.A4") (pin "3") (pinfunction "PA2_3") (pintype "unspecified"))
      (node (ref "U8") (pin "37") (pinfunction "37_37") (pintype "unspecified"))
    )
    (net (code "55") (name "/D.A1") (class "Default")
      (node (ref "H3") (pin "6") (pinfunction "6_6") (pintype "input"))
      (node (ref "U.A4") (pin "2") (pinfunction "PA1_2") (pintype "unspecified"))
      (node (ref "U9") (pin "38") (pinfunction "38_38") (pintype "unspecified"))
    )
    (net (code "56") (name "/D.A2") (class "Default")
      (node (ref "U.A4") (pin "11") (pinfunction "PC4_11") (pintype "unspecified"))
      (node (ref "U8") (pin "43") (pinfunction "43_43") (pintype "unspecified"))
    )
    (net (code "57") (name "/D.A3") (class "Default")
      (node (ref "U.A4") (pin "16") (pinfunction "PD2_16") (pintype "unspecified"))
      (node (ref "U9") (pin "6") (pinfunction "6_6") (pintype "unspecified"))
    )
    (net (code "58") (name "/D.A4") (class "Default")
      (node (ref "U.A4") (pin "17") (pinfunction "PD3_17") (pintype "unspecified"))
      (node (ref "U9") (pin "8") (pinfunction "8_8") (pintype "unspecified"))
    )
    (net (code "59") (name "/D.A5") (class "Default")
      (node (ref "U.A4") (pin "19") (pinfunction "PD5_19") (pintype "unspecified"))
      (node (ref "U9") (pin "12") (pinfunction "12_12") (pintype "unspecified"))
    )
    (net (code "60") (name "/D.A6") (class "Default")
      (node (ref "U.A4") (pin "20") (pinfunction "PD6_20") (pintype "unspecified"))
      (node (ref "U9") (pin "14") (pinfunction "14_14") (pintype "unspecified"))
    )
    (net (code "61") (name "/D.A7") (class "Default")
      (node (ref "U.A4") (pin "18") (pinfunction "PD4_18") (pintype "unspecified"))
      (node (ref "U9") (pin "10") (pinfunction "10_10") (pintype "unspecified"))
    )
    (net (code "62") (name "/D.NRST") (class "Default")
      (node (ref "R33") (pin "2") (pinfunction "2_2") (pintype "input"))
      (node (ref "U1") (pin "21") (pinfunction "IO7_21") (pintype "unspecified"))
    )
    (net (code "63") (name "/D.PC0") (class "Default")
      (node (ref "R35") (pin "2") (pinfunction "2_2") (pintype "input"))
      (node (ref "U.A4") (pin "7") (pinfunction "PC0_7") (pintype "unspecified"))
      (node (ref "U8") (pin "41") (pinfunction "41_41") (pintype "unspecified"))
    )
    (net (code "64") (name "/D.PC3") (class "Default")
      (node (ref "U.A4") (pin "10") (pinfunction "PC3_10") (pintype "unspecified"))
      (node (ref "U8") (pin "45") (pinfunction "45_45") (pintype "unspecified"))
    )
    (net (code "65") (name "/D.PC5.FT") (class "Default")
      (node (ref "H3") (pin "10") (pinfunction "10_10") (pintype "input"))
      (node (ref "U.A4") (pin "12") (pinfunction "PC5_12") (pintype "unspecified"))
      (node (ref "U8") (pin "42") (pinfunction "42_42") (pintype "unspecified"))
    )
    (net (code "66") (name "/D.PC6.FT") (class "Default")
      (node (ref "H3") (pin "12") (pinfunction "12_12") (pintype "input"))
      (node (ref "U.A4") (pin "13") (pinfunction "PC6_13") (pintype "unspecified"))
      (node (ref "U8") (pin "40") (pinfunction "40_40") (pintype "unspecified"))
    )
    (net (code "67") (name "/D.PC7") (class "Default")
      (node (ref "U.A4") (pin "14") (pinfunction "PC7_14") (pintype "unspecified"))
      (node (ref "U9") (pin "4") (pinfunction "4_4") (pintype "unspecified"))
    )
    (net (code "68") (name "/D.PD0") (class "Default")
      (node (ref "U.A4") (pin "5") (pinfunction "PD0_5") (pintype "unspecified"))
      (node (ref "U8") (pin "39") (pinfunction "39_39") (pintype "unspecified"))
    )
    (net (code "69") (name "/D.SWIO") (class "Default")
      (node (ref "FPC1") (pin "2") (pinfunction "2_2") (pintype "unspecified"))
      (node (ref "U.A4") (pin "15") (pinfunction "PD1_15") (pintype "unspecified"))
    )
    (net (code "70") (name "/E.A0") (class "Default")
      (node (ref "U.A5") (pin "3") (pinfunction "PA2_3") (pintype "unspecified"))
      (node (ref "U9") (pin "32") (pinfunction "32_32") (pintype "unspecified"))
    )
    (net (code "71") (name "/E.A1") (class "Default")
      (node (ref "U.A5") (pin "2") (pinfunction "PA1_2") (pintype "unspecified"))
      (node (ref "U8") (pin "31") (pinfunction "31_31") (pintype "unspecified"))
    )
    (net (code "72") (name "/E.A2") (class "Default")
      (node (ref "U.A5") (pin "11") (pinfunction "PC4_11") (pintype "unspecified"))
      (node (ref "U9") (pin "35") (pinfunction "35_35") (pintype "unspecified"))
    )
    (net (code "73") (name "/E.A3") (class "Default")
      (node (ref "U.A5") (pin "16") (pinfunction "PD2_16") (pintype "unspecified"))
      (node (ref "U9") (pin "31") (pinfunction "31_31") (pintype "unspecified"))
    )
    (net (code "74") (name "/E.A4") (class "Default")
      (node (ref "U.A5") (pin "17") (pinfunction "PD3_17") (pintype "unspecified"))
      (node (ref "U9") (pin "29") (pinfunction "29_29") (pintype "unspecified"))
    )
    (net (code "75") (name "/E.A5") (class "Default")
      (node (ref "U.A5") (pin "19") (pinfunction "PD5_19") (pintype "unspecified"))
      (node (ref "U9") (pin "25") (pinfunction "25_25") (pintype "unspecified"))
    )
    (net (code "76") (name "/E.A6") (class "Default")
      (node (ref "U.A5") (pin "20") (pinfunction "PD6_20") (pintype "unspecified"))
      (node (ref "U9") (pin "23") (pinfunction "23_23") (pintype "unspecified"))
    )
    (net (code "77") (name "/E.A7") (class "Default")
      (node (ref "U.A5") (pin "18") (pinfunction "PD4_18") (pintype "unspecified"))
      (node (ref "U9") (pin "27") (pinfunction "27_27") (pintype "unspecified"))
    )
    (net (code "78") (name "/E.NRST") (class "Default")
      (node (ref "R36") (pin "2") (pinfunction "2_2") (pintype "input"))
      (node (ref "U1") (pin "19") (pinfunction "IO5_19") (pintype "unspecified"))
    )
    (net (code "79") (name "/E.PC0") (class "Default")
      (node (ref "R38") (pin "2") (pinfunction "2_2") (pintype "input"))
      (node (ref "U.A5") (pin "7") (pinfunction "PC0_7") (pintype "unspecified"))
      (node (ref "U9") (pin "18") (pinfunction "18_18") (pintype "unspecified"))
    )
    (net (code "80") (name "/E.PC3") (class "Default")
      (node (ref "U.A5") (pin "10") (pinfunction "PC3_10") (pintype "unspecified"))
      (node (ref "U9") (pin "37") (pinfunction "37_37") (pintype "unspecified"))
    )
    (net (code "81") (name "/E.PC5.FT") (class "Default")
      (node (ref "U.A5") (pin "12") (pinfunction "PC5_12") (pintype "unspecified"))
      (node (ref "U8") (pin "38") (pinfunction "38_38") (pintype "unspecified"))
    )
    (net (code "82") (name "/E.PC6.FT") (class "Default")
      (node (ref "U.A5") (pin "13") (pinfunction "PC6_13") (pintype "unspecified"))
      (node (ref "U8") (pin "36") (pinfunction "36_36") (pintype "unspecified"))
    )
    (net (code "83") (name "/E.PC7") (class "Default")
      (node (ref "U.A5") (pin "14") (pinfunction "PC7_14") (pintype "unspecified"))
      (node (ref "U9") (pin "33") (pinfunction "33_33") (pintype "unspecified"))
    )
    (net (code "84") (name "/E.PD0") (class "Default")
      (node (ref "U.A5") (pin "5") (pinfunction "PD0_5") (pintype "unspecified"))
      (node (ref "U9") (pin "16") (pinfunction "16_16") (pintype "unspecified"))
    )
    (net (code "85") (name "/E.SWIO") (class "Default")
      (node (ref "FPC1") (pin "3") (pinfunction "3_3") (pintype "unspecified"))
      (node (ref "U.A5") (pin "15") (pinfunction "PD1_15") (pintype "unspecified"))
    )
    (net (code "86") (name "/EN") (class "Default")
      (node (ref "C1") (pin "1") (pinfunction "1_1") (pintype "input"))
      (node (ref "C20") (pin "1") (pinfunction "1_1") (pintype "input"))
      (node (ref "H3") (pin "9") (pinfunction "9_9") (pintype "input"))
      (node (ref "R4") (pin "1") (pinfunction "1_1") (pintype "input"))
      (node (ref "SW1") (pin "2") (pinfunction "2_2") (pintype "input"))
      (node (ref "SW1") (pin "4") (pinfunction "4_4") (pintype "input"))
      (node (ref "U1") (pin "8") (pinfunction "EN_8") (pintype "unspecified"))
      (node (ref "U9") (pin "47") (pinfunction "47_47") (pintype "unspecified"))
    )
    (net (code "87") (name "/GPIO9{slash}BOOT") (class "Default")
      (node (ref "R17") (pin "1") (pinfunction "1_1") (pintype "input"))
      (node (ref "SW2") (pin "2") (pinfunction "2_2") (pintype "input"))
      (node (ref "SW2") (pin "4") (pinfunction "4_4") (pintype "input"))
      (node (ref "U1") (pin "23") (pinfunction "IO9_23") (pintype "unspecified"))
      (node (ref "U9") (pin "49") (pinfunction "49_49") (pintype "unspecified"))
    )
    (net (code "88") (name "/IO0") (class "Default")
      (node (ref "H3") (pin "1") (pinfunction "1_1") (pintype "input"))
      (node (ref "U1") (pin "12") (pinfunction "IO0_12") (pintype "unspecified"))
      (node (ref "U9") (pin "45") (pinfunction "45_45") (pintype "unspecified"))
    )
    (net (code "89") (name "/IO2") (class "Default")
      (node (ref "R18") (pin "1") (pinfunction "1_1") (pintype "input"))
      (node (ref "U1") (pin "5") (pinfunction "IO2_5") (pintype "unspecified"))
      (node (ref "U9") (pin "43") (pinfunction "43_43") (pintype "unspecified"))
    )
    (net (code "90") (name "/IO3") (class "Default")
      (node (ref "H3") (pin "3") (pinfunction "3_3") (pintype "input"))
      (node (ref "U1") (pin "6") (pinfunction "IO3_6") (pintype "unspecified"))
      (node (ref "U9") (pin "41") (pinfunction "41_41") (pintype "unspecified"))
    )
    (net (code "91") (name "/RXD0") (class "Default")
      (node (ref "FPC2") (pin "3") (pinfunction "3_3") (pintype "input"))
      (node (ref "H3") (pin "14") (pinfunction "14_14") (pintype "input"))
      (node (ref "U1") (pin "30") (pinfunction "RXD0_30") (pintype "unspecified"))
      (node (ref "U9") (pin "50") (pinfunction "50_50") (pintype "unspecified"))
    )
    (net (code "92") (name "/SCL") (class "Default")
      (node (ref "FPC2") (pin "4") (pinfunction "4_4") (pintype "input"))
      (node (ref "H3") (pin "7") (pinfunction "7_7") (pintype "input"))
      (node (ref "R20") (pin "1") (pinfunction "1_1") (pintype "input"))
      (node (ref "U.A1") (pin "9") (pinfunction "PC2_9") (pintype "unspecified"))
      (node (ref "U.A2") (pin "9") (pinfunction "PC2_9") (pintype "unspecified"))
      (node (ref "U.A3") (pin "9") (pinfunction "PC2_9") (pintype "unspecified"))
      (node (ref "U.A4") (pin "9") (pinfunction "PC2_9") (pintype "unspecified"))
      (node (ref "U.A5") (pin "9") (pinfunction "PC2_9") (pintype "unspecified"))
      (node (ref "U1") (pin "22") (pinfunction "IO8_22") (pintype "unspecified"))
      (node (ref "U9") (pin "44") (pinfunction "44_44") (pintype "unspecified"))
    )
    (net (code "93") (name "/SDA") (class "Default")
      (node (ref "FPC2") (pin "5") (pinfunction "5_5") (pintype "input"))
      (node (ref "H3") (pin "5") (pinfunction "5_5") (pintype "input"))
      (node (ref "R19") (pin "1") (pinfunction "1_1") (pintype "input"))
      (node (ref "U.A1") (pin "8") (pinfunction "PC1_8") (pintype "unspecified"))
      (node (ref "U.A2") (pin "8") (pinfunction "PC1_8") (pintype "unspecified"))
      (node (ref "U.A3") (pin "8") (pinfunction "PC1_8") (pintype "unspecified"))
      (node (ref "U.A4") (pin "8") (pinfunction "PC1_8") (pintype "unspecified"))
      (node (ref "U.A5") (pin "8") (pinfunction "PC1_8") (pintype "unspecified"))
      (node (ref "U1") (pin "16") (pinfunction "IO10_16") (pintype "unspecified"))
      (node (ref "U9") (pin "42") (pinfunction "42_42") (pintype "unspecified"))
    )
    (net (code "94") (name "/TXD0") (class "Default")
      (node (ref "FPC2") (pin "2") (pinfunction "2_2") (pintype "input"))
      (node (ref "H3") (pin "16") (pinfunction "16_16") (pintype "input"))
      (node (ref "U1") (pin "31") (pinfunction "TXD0_31") (pintype "unspecified"))
      (node (ref "U9") (pin "48") (pinfunction "48_48") (pintype "unspecified"))
    )
    (net (code "95") (name "/USB_D+") (class "Default")
      (node (ref "R8") (pin "1") (pinfunction "1_1") (pintype "input"))
      (node (ref "U1") (pin "27") (pinfunction "IO19_27") (pintype "unspecified"))
    )
    (net (code "96") (name "/USB_D-") (class "Default")
      (node (ref "R7") (pin "1") (pinfunction "1_1") (pintype "input"))
      (node (ref "U1") (pin "26") (pinfunction "IO18_26") (pintype "unspecified"))
    )
    (net (code "97") (name "/VBUS_USB") (class "Default")
      (node (ref "D3") (pin "2") (pinfunction "A_2") (pintype "unspecified"))
      (node (ref "U2") (pin "2") (pinfunction "2_2") (pintype "unspecified"))
      (node (ref "USB1") (pin "11") (pinfunction "VBUS_11") (pintype "unspecified"))
      (node (ref "USB1") (pin "2") (pinfunction "VBUS_2") (pintype "unspecified"))
    )
    (net (code "98") (name "GND") (class "Default")
      (node (ref "C1") (pin "2") (pinfunction "2_2") (pintype "input"))
      (node (ref "C2") (pin "2") (pinfunction "2_2") (pintype "input"))
      (node (ref "C20") (pin "2") (pinfunction "2_2") (pintype "input"))
      (node (ref "C22") (pin "2") (pinfunction "2_2") (pintype "input"))
      (node (ref "C23") (pin "2") (pinfunction "2_2") (pintype "input"))
      (node (ref "C24") (pin "2") (pinfunction "2_2") (pintype "input"))
      (node (ref "C25") (pin "2") (pinfunction "2_2") (pintype "input"))
      (node (ref "C26") (pin "2") (pinfunction "2_2") (pintype "input"))
      (node (ref "C27") (pin "2") (pinfunction "2_2") (pintype "input"))
      (node (ref "C28") (pin "2") (pinfunction "2_2") (pintype "input"))
      (node (ref "C29") (pin "2") (pinfunction "2_2") (pintype "input"))
      (node (ref "C3") (pin "2") (pinfunction "2_2") (pintype "input"))
      (node (ref "C30") (pin "2") (pinfunction "2_2") (pintype "input"))
      (node (ref "C31") (pin "2") (pinfunction "2_2") (pintype "input"))
      (node (ref "C4") (pin "2") (pinfunction "2_2") (pintype "input"))
      (node (ref "C5") (pin "2") (pinfunction "2_2") (pintype "input"))
      (node (ref "D1") (pin "1") (pinfunction "1_1") (pintype "unspecified"))
      (node (ref "D4") (pin "1") (pinfunction "1_1") (pintype "unspecified"))
      (node (ref "FPC1") (pin "10") (pinfunction "10_10") (pintype "unspecified"))
      (node (ref "FPC1") (pin "8") (pinfunction "8_8") (pintype "unspecified"))
      (node (ref "FPC1") (pin "9") (pinfunction "9_9") (pintype "unspecified"))
      (node (ref "FPC2") (pin "1") (pinfunction "1_1") (pintype "input"))
      (node (ref "FPC2") (pin "7") (pinfunction "7_7") (pintype "input"))
      (node (ref "FPC2") (pin "8") (pinfunction "8_8") (pintype "input"))
      (node (ref "FPC3") (pin "1") (pinfunction "1_1") (pintype "input"))
      (node (ref "FPC3") (pin "2") (pinfunction "2_2") (pintype "input"))
      (node (ref "FPC3") (pin "39") (pinfunction "39_39") (pintype "input"))
      (node (ref "FPC3") (pin "40") (pinfunction "40_40") (pintype "input"))
      (node (ref "FPC3") (pin "41") (pinfunction "41_41") (pintype "input"))
      (node (ref "FPC3") (pin "42") (pinfunction "42_42") (pintype "input"))
      (node (ref "H3") (pin "13") (pinfunction "13_13") (pintype "input"))
      (node (ref "H3") (pin "15") (pinfunction "15_15") (pintype "input"))
      (node (ref "LED2") (pin "2") (pinfunction "A_2") (pintype "unspecified"))
      (node (ref "LED3") (pin "2") (pinfunction "A_2") (pintype "unspecified"))
      (node (ref "LED4") (pin "2") (pinfunction "A_2") (pintype "unspecified"))
      (node (ref "LED5") (pin "2") (pinfunction "A_2") (pintype "unspecified"))
      (node (ref "LED6") (pin "2") (pinfunction "A_2") (pintype "unspecified"))
      (node (ref "R44") (pin "1") (pinfunction "1_1") (pintype "input"))
      (node (ref "R45") (pin "1") (pinfunction "1_1") (pintype "input"))
      (node (ref "R5") (pin "1") (pinfunction "1_1") (pintype "input"))
      (node (ref "R6") (pin "1") (pinfunction "1_1") (pintype "input"))
      (node (ref "SW1") (pin "1") (pinfunction "1_1") (pintype "input"))
      (node (ref "SW1") (pin "3") (pinfunction "3_3") (pintype "input"))
      (node (ref "SW2") (pin "1") (pinfunction "1_1") (pintype "input"))
      (node (ref "SW2") (pin "3") (pinfunction "3_3") (pintype "input"))
      (node (ref "U.A1") (pin "21") (pinfunction "VSS_21") (pintype "unspecified"))
      (node (ref "U.A1") (pin "4") (pinfunction "VSS_4") (pintype "unspecified"))
      (node (ref "U.A2") (pin "21") (pinfunction "VSS_21") (pintype "unspecified"))
      (node (ref "U.A2") (pin "4") (pinfunction "VSS_4") (pintype "unspecified"))
      (node (ref "U.A3") (pin "21") (pinfunction "VSS_21") (pintype "unspecified"))
      (node (ref "U.A3") (pin "4") (pinfunction "VSS_4") (pintype "unspecified"))
      (node (ref "U.A4") (pin "21") (pinfunction "VSS_21") (pintype "unspecified"))
      (node (ref "U.A4") (pin "4") (pinfunction "VSS_4") (pintype "unspecified"))
      (node (ref "U.A5") (pin "21") (pinfunction "VSS_21") (pintype "unspecified"))
      (node (ref "U.A5") (pin "4") (pinfunction "VSS_4") (pintype "unspecified"))
      (node (ref "U1") (pin "1") (pinfunction "GND_1") (pintype "unspecified"))
      (node (ref "U1") (pin "11") (pinfunction "GND_11") (pintype "unspecified"))
      (node (ref "U1") (pin "14") (pinfunction "GND_14") (pintype "unspecified"))
      (node (ref "U1") (pin "2") (pinfunction "GND_2") (pintype "unspecified"))
      (node (ref "U1") (pin "36") (pinfunction "GND_36") (pintype "unspecified"))
      (node (ref "U1") (pin "37") (pinfunction "GND_37") (pintype "unspecified"))
      (node (ref "U1") (pin "38") (pinfunction "GND_38") (pintype "unspecified"))
      (node (ref "U1") (pin "39") (pinfunction "GND_39") (pintype "unspecified"))
      (node (ref "U1") (pin "40") (pinfunction "GND_40") (pintype "unspecified"))
      (node (ref "U1") (pin "41") (pinfunction "GND_41") (pintype "unspecified"))
      (node (ref "U1") (pin "42") (pinfunction "GND_42") (pintype "unspecified"))
      (node (ref "U1") (pin "43") (pinfunction "GND_43") (pintype "unspecified"))
      (node (ref "U1") (pin "44") (pinfunction "GND_44") (pintype "unspecified"))
      (node (ref "U1") (pin "45") (pinfunction "GND_45") (pintype "unspecified"))
      (node (ref "U1") (pin "46") (pinfunction "GND_46") (pintype "unspecified"))
      (node (ref "U1") (pin "47") (pinfunction "GND_47") (pintype "unspecified"))
      (node (ref "U1") (pin "48") (pinfunction "GND_48") (pintype "unspecified"))
      (node (ref "U1") (pin "49") (pinfunction "GND_49") (pintype "unspecified"))
      (node (ref "U1") (pin "50") (pinfunction "GND_50") (pintype "unspecified"))
      (node (ref "U1") (pin "51") (pinfunction "GND_51") (pintype "unspecified"))
      (node (ref "U1") (pin "52") (pinfunction "GND_52") (pintype "unspecified"))
      (node (ref "U1") (pin "53") (pinfunction "GND_53") (pintype "unspecified"))
      (node (ref "U13") (pin "2") (pinfunction "GND_2") (pintype "unspecified"))
      (node (ref "U2") (pin "1") (pinfunction "1_1") (pintype "unspecified"))
      (node (ref "U3") (pin "1") (pinfunction "1_1") (pintype "unspecified"))
      (node (ref "U4") (pin "1") (pinfunction "1_1") (pintype "unspecified"))
      (node (ref "U8") (pin "19") (pinfunction "19_19") (pintype "unspecified"))
      (node (ref "U8") (pin "20") (pinfunction "20_20") (pintype "unspecified"))
      (node (ref "U8") (pin "21") (pinfunction "21_21") (pintype "unspecified"))
      (node (ref "U8") (pin "22") (pinfunction "22_22") (pintype "unspecified"))
      (node (ref "U9") (pin "19") (pinfunction "19_19") (pintype "unspecified"))
      (node (ref "U9") (pin "20") (pinfunction "20_20") (pintype "unspecified"))
      (node (ref "U9") (pin "21") (pinfunction "21_21") (pintype "unspecified"))
      (node (ref "U9") (pin "22") (pinfunction "22_22") (pintype "unspecified"))
      (node (ref "U9") (pin "46") (pinfunction "46_46") (pintype "unspecified"))
      (node (ref "USB1") (pin "1") (pinfunction "GND_1") (pintype "unspecified"))
      (node (ref "USB1") (pin "12") (pinfunction "GND_12") (pintype "unspecified"))
      (node (ref "USB1") (pin "13") (pinfunction "SHELL_13") (pintype "unspecified"))
      (node (ref "USB1") (pin "14") (pinfunction "SHELL_14") (pintype "unspecified"))
    )
    (net (code "99") (name "Net-(LED2-K)") (class "Default")
      (node (ref "LED2") (pin "1") (pinfunction "K_1") (pintype "unspecified"))
      (node (ref "R26") (pin "1") (pinfunction "1_1") (pintype "input"))
    )
    (net (code "100") (name "Net-(LED3-K)") (class "Default")
      (node (ref "LED3") (pin "1") (pinfunction "K_1") (pintype "unspecified"))
      (node (ref "R29") (pin "1") (pinfunction "1_1") (pintype "input"))
    )
    (net (code "101") (name "Net-(LED4-K)") (class "Default")
      (node (ref "LED4") (pin "1") (pinfunction "K_1") (pintype "unspecified"))
      (node (ref "R32") (pin "1") (pinfunction "1_1") (pintype "input"))
    )
    (net (code "102") (name "Net-(LED5-K)") (class "Default")
      (node (ref "LED5") (pin "1") (pinfunction "K_1") (pintype "unspecified"))
      (node (ref "R35") (pin "1") (pinfunction "1_1") (pintype "input"))
    )
    (net (code "103") (name "Net-(LED6-K)") (class "Default")
      (node (ref "LED6") (pin "1") (pinfunction "K_1") (pintype "unspecified"))
      (node (ref "R38") (pin "1") (pinfunction "1_1") (pintype "input"))
    )
    (net (code "104") (name "Net-(Q14-G)") (class "Default")
      (node (ref "Q14") (pin "1") (pinfunction "G_1") (pintype "unspecified"))
      (node (ref "R44") (pin "2") (pinfunction "2_2") (pintype "input"))
      (node (ref "U14") (pin "3") (pinfunction "BIAS_3") (pintype "unspecified"))
    )
    (net (code "105") (name "Net-(U.A1-PD7)") (class "Default")
      (node (ref "R24") (pin "1") (pinfunction "1_1") (pintype "input"))
      (node (ref "R25") (pin "1") (pinfunction "1_1") (pintype "input"))
      (node (ref "U.A1") (pin "1") (pinfunction "PD7_1") (pintype "unspecified"))
    )
    (net (code "106") (name "Net-(U.A2-PD7)") (class "Default")
      (node (ref "R27") (pin "1") (pinfunction "1_1") (pintype "input"))
      (node (ref "R28") (pin "1") (pinfunction "1_1") (pintype "input"))
      (node (ref "U.A2") (pin "1") (pinfunction "PD7_1") (pintype "unspecified"))
    )
    (net (code "107") (name "Net-(U.A3-PD7)") (class "Default")
      (node (ref "R30") (pin "1") (pinfunction "1_1") (pintype "input"))
      (node (ref "R31") (pin "1") (pinfunction "1_1") (pintype "input"))
      (node (ref "U.A3") (pin "1") (pinfunction "PD7_1") (pintype "unspecified"))
    )
    (net (code "108") (name "Net-(U.A4-PD7)") (class "Default")
      (node (ref "R33") (pin "1") (pinfunction "1_1") (pintype "input"))
      (node (ref "R34") (pin "1") (pinfunction "1_1") (pintype "input"))
      (node (ref "U.A4") (pin "1") (pinfunction "PD7_1") (pintype "unspecified"))
    )
    (net (code "109") (name "Net-(U.A5-PD7)") (class "Default")
      (node (ref "R36") (pin "1") (pinfunction "1_1") (pintype "input"))
      (node (ref "R37") (pin "1") (pinfunction "1_1") (pintype "input"))
      (node (ref "U.A5") (pin "1") (pinfunction "PD7_1") (pintype "unspecified"))
    )
    (net (code "110") (name "Net-(U14-REF)") (class "Default")
      (node (ref "R45") (pin "2") (pinfunction "2_2") (pintype "input"))
      (node (ref "U14") (pin "2") (pinfunction "REF_2") (pintype "unspecified"))
    )
    (net (code "111") (name "Net-(USB1-DN1)") (class "Default")
      (node (ref "R7") (pin "2") (pinfunction "2_2") (pintype "input"))
      (node (ref "U4") (pin "2") (pinfunction "2_2") (pintype "unspecified"))
      (node (ref "USB1") (pin "5") (pinfunction "DN2_5") (pintype "unspecified"))
      (node (ref "USB1") (pin "7") (pinfunction "DN1_7") (pintype "unspecified"))
    )
    (net (code "112") (name "Net-(USB1-DP1)") (class "Default")
      (node (ref "R8") (pin "2") (pinfunction "2_2") (pintype "input"))
      (node (ref "U3") (pin "2") (pinfunction "2_2") (pintype "unspecified"))
      (node (ref "USB1") (pin "6") (pinfunction "DP1_6") (pintype "unspecified"))
      (node (ref "USB1") (pin "8") (pinfunction "DP2_8") (pintype "unspecified"))
    )
    (net (code "113") (name "unconnected-(FPC1-Pad7)") (class "Default")
      (node (ref "FPC1") (pin "7") (pinfunction "7_7") (pintype "unspecified"))
    )
    (net (code "114") (name "unconnected-(SW1-Pad5)") (class "Default")
      (node (ref "SW1") (pin "5") (pinfunction "5_5") (pintype "input+no_connect"))
    )
    (net (code "115") (name "unconnected-(SW1-Pad6)") (class "Default")
      (node (ref "SW1") (pin "6") (pinfunction "6_6") (pintype "input+no_connect"))
    )
    (net (code "116") (name "unconnected-(SW2-Pad5)") (class "Default")
      (node (ref "SW2") (pin "5") (pinfunction "5_5") (pintype "input+no_connect"))
    )
    (net (code "117") (name "unconnected-(SW2-Pad6)") (class "Default")
      (node (ref "SW2") (pin "6") (pinfunction "6_6") (pintype "input+no_connect"))
    )
    (net (code "118") (name "unconnected-(U1-NC-Pad4)") (class "Default")
      (node (ref "U1") (pin "4") (pinfunction "NC_4") (pintype "unspecified+no_connect"))
    )
    (net (code "119") (name "unconnected-(U1-NC-Pad7)") (class "Default")
      (node (ref "U1") (pin "7") (pinfunction "NC_7") (pintype "unspecified+no_connect"))
    )
    (net (code "120") (name "unconnected-(U1-NC-Pad9)") (class "Default")
      (node (ref "U1") (pin "9") (pinfunction "NC_9") (pintype "unspecified+no_connect"))
    )
    (net (code "121") (name "unconnected-(U1-NC-Pad10)") (class "Default")
      (node (ref "U1") (pin "10") (pinfunction "NC_10") (pintype "unspecified+no_connect"))
    )
    (net (code "122") (name "unconnected-(U1-NC-Pad15)") (class "Default")
      (node (ref "U1") (pin "15") (pinfunction "NC_15") (pintype "unspecified+no_connect"))
    )
    (net (code "123") (name "unconnected-(U1-NC-Pad17)") (class "Default")
      (node (ref "U1") (pin "17") (pinfunction "NC_17") (pintype "unspecified+no_connect"))
    )
    (net (code "124") (name "unconnected-(U1-NC-Pad24)") (class "Default")
      (node (ref "U1") (pin "24") (pinfunction "NC_24") (pintype "unspecified+no_connect"))
    )
    (net (code "125") (name "unconnected-(U1-NC-Pad25)") (class "Default")
      (node (ref "U1") (pin "25") (pinfunction "NC_25") (pintype "unspecified+no_connect"))
    )
    (net (code "126") (name "unconnected-(U1-NC-Pad28)") (class "Default")
      (node (ref "U1") (pin "28") (pinfunction "NC_28") (pintype "unspecified+no_connect"))
    )
    (net (code "127") (name "unconnected-(U1-NC-Pad29)") (class "Default")
      (node (ref "U1") (pin "29") (pinfunction "NC_29") (pintype "unspecified+no_connect"))
    )
    (net (code "128") (name "unconnected-(U1-NC-Pad32)") (class "Default")
      (node (ref "U1") (pin "32") (pinfunction "NC_32") (pintype "unspecified+no_connect"))
    )
    (net (code "129") (name "unconnected-(U1-NC-Pad33)") (class "Default")
      (node (ref "U1") (pin "33") (pinfunction "NC_33") (pintype "unspecified+no_connect"))
    )
    (net (code "130") (name "unconnected-(U1-NC-Pad34)") (class "Default")
      (node (ref "U1") (pin "34") (pinfunction "NC_34") (pintype "unspecified+no_connect"))
    )
    (net (code "131") (name "unconnected-(U1-NC-Pad35)") (class "Default")
      (node (ref "U1") (pin "35") (pinfunction "NC_35") (pintype "unspecified+no_connect"))
    )
    (net (code "132") (name "unconnected-(U13-NC-Pad4)") (class "Default")
      (node (ref "U13") (pin "4") (pinfunction "NC_4") (pintype "unspecified+no_connect"))
    )
    (net (code "133") (name "unconnected-(U14-NC-Pad1)") (class "Default")
      (node (ref "U14") (pin "1") (pinfunction "NC_1") (pintype "unspecified+no_connect"))
    )
    (net (code "134") (name "unconnected-(U14-NC-Pad5)") (class "Default")
      (node (ref "U14") (pin "5") (pinfunction "NC_5") (pintype "unspecified+no_connect"))
    )
    (net (code "135") (name "unconnected-(USB1-SBU1-Pad9)") (class "Default")
      (node (ref "USB1") (pin "9") (pinfunction "SBU1_9") (pintype "unspecified+no_connect"))
    )
    (net (code "136") (name "unconnected-(USB1-SBU2-Pad3)") (class "Default")
      (node (ref "USB1") (pin "3") (pinfunction "SBU2_3") (pintype "unspecified+no_connect"))
    )
  )
)
